# ATtiny_dev_board.net
KiCad netlist of a schematic drawn in EAGLE
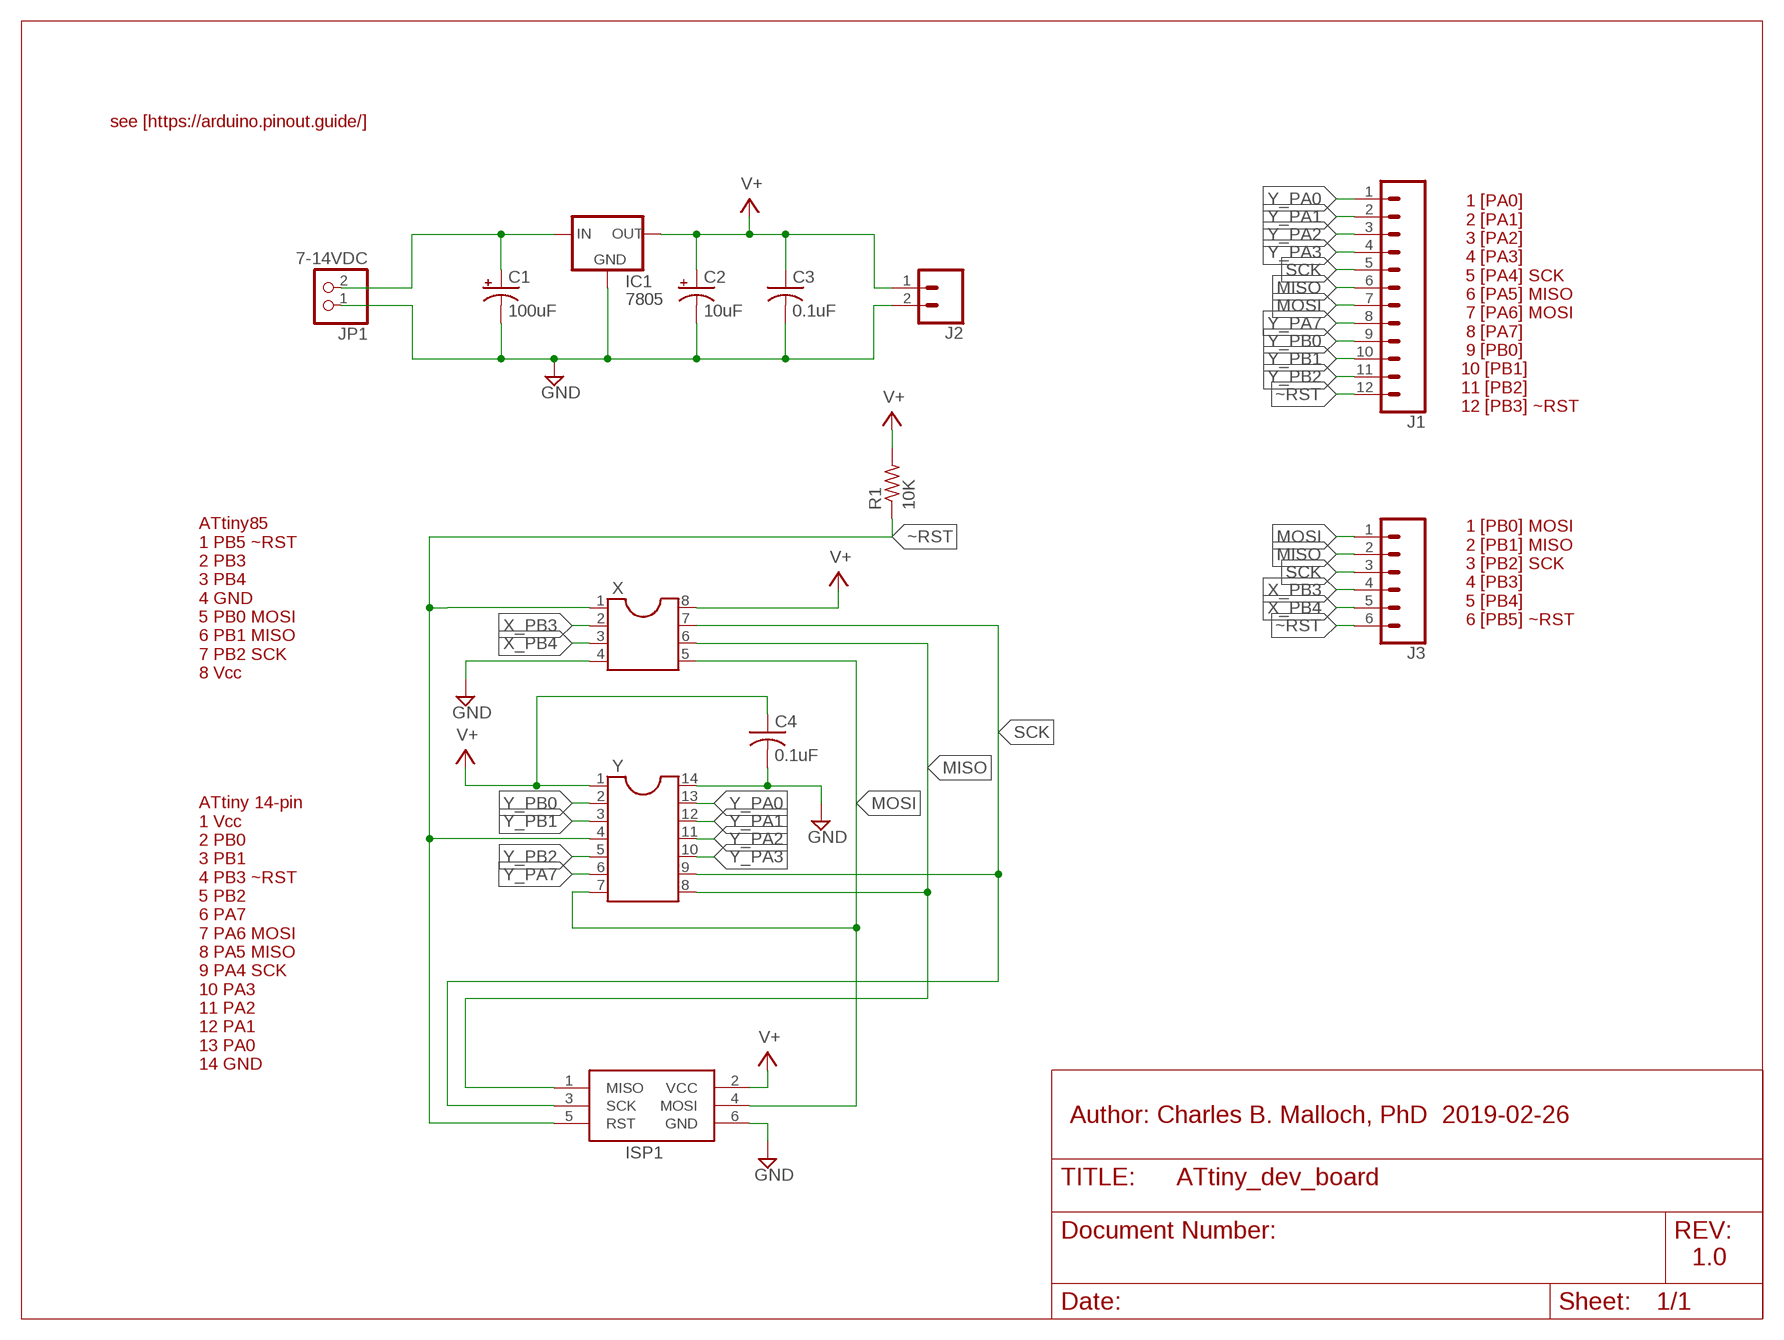
[diagram p0: schematic, sheet 1]

(export (version "E")
  (design (tool "Eeschema 10.0.6"))
  (components
    (comp (ref "C1")
      (value "100uF")
      (footprint "eagle-import:TT2D7")
      (libsource (lib "eagle-import") (part "CPOL-USTT2D7"))
    )
    (comp (ref "C2")
      (value "10uF")
      (footprint "eagle-import:E1,8-4")
      (libsource (lib "eagle-import") (part "CPOL-USE1.8-4"))
    )
    (comp (ref "C3")
      (value "0.1uF")
      (footprint "eagle-import:C025-025X050")
      (libsource (lib "eagle-import") (part "C-US025-025X050"))
    )
    (comp (ref "C4")
      (value "0.1uF")
      (footprint "eagle-import:C025-025X050")
      (libsource (lib "eagle-import") (part "C-US025-025X050"))
    )
    (comp (ref "IC1")
      (value "7805")
      (footprint "eagle-import:TO-220-ALT")
      (libsource (lib "eagle-import") (part "V_REG_78XX-TO-220"))
    )
    (comp (ref "ISP1")
      (value "AVRISP-BOX")
      (footprint "eagle-import:AVRISP-BOX")
      (libsource (lib "eagle-import") (part "AVRISP-BOX"))
    )
    (comp (ref "J1")
      (value "CONN_12LOCK_LONGPADS")
      (footprint "eagle-import:1X12_LOCK_LONGPADS")
      (libsource (lib "eagle-import") (part "CONN_12LOCK_LONGPADS"))
    )
    (comp (ref "J2")
      (value "CONN_02LOCK_LONGPADS")
      (footprint "eagle-import:1X02_LOCK_LONGPADS")
      (libsource (lib "eagle-import") (part "CONN_02LOCK_LONGPADS"))
    )
    (comp (ref "J3")
      (value "CONN_06LOCK_LONGPADS")
      (footprint "eagle-import:1X06_LOCK_LONGPADS")
      (libsource (lib "eagle-import") (part "CONN_06LOCK_LONGPADS"))
    )
    (comp (ref "JP1")
      (value "7-14VDC")
      (footprint "eagle-import:1X02")
      (libsource (lib "eagle-import") (part "PINHD-1X2"))
    )
    (comp (ref "R1")
      (value "10K")
      (footprint "eagle-import:0309_12")
      (libsource (lib "eagle-import") (part "R-US_0309/12"))
    )
    (comp (ref "X")
      (value "DIL8S")
      (footprint "eagle-import:SOCKET-08")
      (libsource (lib "eagle-import") (part "DIL8S"))
    )
    (comp (ref "Y")
      (value "DIL14S")
      (footprint "eagle-import:SOCKET-14")
      (libsource (lib "eagle-import") (part "DIL14S"))
    )
  )
  (nets
    (net (code "1") (name "/~{RST}") (class "Default")
      (node (ref "ISP1") (pin "5") (pinfunction "RST_5") (pintype "output"))
      (node (ref "J1") (pin "12") (pinfunction "12_12") (pintype "passive"))
      (node (ref "J3") (pin "6") (pinfunction "6_6") (pintype "passive"))
      (node (ref "R1") (pin "1") (pinfunction "1_1") (pintype "passive"))
      (node (ref "X") (pin "1") (pinfunction "1_1") (pintype "passive"))
      (node (ref "Y") (pin "4") (pinfunction "4_4") (pintype "passive"))
    )
    (net (code "2") (name "GND") (class "Default")
      (node (ref "C1") (pin "-") (pinfunction "-_-") (pintype "passive"))
      (node (ref "C2") (pin "-") (pinfunction "-_-") (pintype "passive"))
      (node (ref "C3") (pin "2") (pinfunction "2_2") (pintype "passive"))
      (node (ref "C4") (pin "2") (pinfunction "2_2") (pintype "passive"))
      (node (ref "IC1") (pin "GND") (pinfunction "GND_GND") (pintype "input"))
      (node (ref "ISP1") (pin "6") (pinfunction "GND_6") (pintype "power_in"))
      (node (ref "J2") (pin "2") (pinfunction "2_2") (pintype "passive"))
      (node (ref "JP1") (pin "1") (pinfunction "1_1") (pintype "passive"))
      (node (ref "X") (pin "4") (pinfunction "4_4") (pintype "passive"))
      (node (ref "Y") (pin "14") (pinfunction "14_14") (pintype "passive"))
    )
    (net (code "3") (name "MISO") (class "Default")
      (node (ref "ISP1") (pin "1") (pinfunction "MISO_1") (pintype "input"))
      (node (ref "J1") (pin "6") (pinfunction "6_6") (pintype "passive"))
      (node (ref "J3") (pin "2") (pinfunction "2_2") (pintype "passive"))
      (node (ref "X") (pin "6") (pinfunction "6_6") (pintype "passive"))
      (node (ref "Y") (pin "8") (pinfunction "8_8") (pintype "passive"))
    )
    (net (code "4") (name "MOSI") (class "Default")
      (node (ref "ISP1") (pin "4") (pinfunction "MOSI_4") (pintype "output"))
      (node (ref "J1") (pin "7") (pinfunction "7_7") (pintype "passive"))
      (node (ref "J3") (pin "1") (pinfunction "1_1") (pintype "passive"))
      (node (ref "X") (pin "5") (pinfunction "5_5") (pintype "passive"))
      (node (ref "Y") (pin "7") (pinfunction "7_7") (pintype "passive"))
    )
    (net (code "5") (name "Net-(C1-Pad+)") (class "Default")
      (node (ref "C1") (pin "+") (pinfunction "+_+") (pintype "passive"))
      (node (ref "IC1") (pin "IN") (pinfunction "IN_IN") (pintype "input"))
      (node (ref "JP1") (pin "2") (pinfunction "2_2") (pintype "passive"))
    )
    (net (code "6") (name "SCK") (class "Default")
      (node (ref "ISP1") (pin "3") (pinfunction "SCK_3") (pintype "output"))
      (node (ref "J1") (pin "5") (pinfunction "5_5") (pintype "passive"))
      (node (ref "J3") (pin "3") (pinfunction "3_3") (pintype "passive"))
      (node (ref "X") (pin "7") (pinfunction "7_7") (pintype "passive"))
      (node (ref "Y") (pin "9") (pinfunction "9_9") (pintype "passive"))
    )
    (net (code "7") (name "V+") (class "Default")
      (node (ref "C2") (pin "+") (pinfunction "+_+") (pintype "passive"))
      (node (ref "C3") (pin "1") (pinfunction "1_1") (pintype "passive"))
      (node (ref "C4") (pin "1") (pinfunction "1_1") (pintype "passive"))
      (node (ref "IC1") (pin "OUT") (pinfunction "OUT_OUT") (pintype "output"))
      (node (ref "ISP1") (pin "2") (pinfunction "VCC_2") (pintype "power_in"))
      (node (ref "J2") (pin "1") (pinfunction "1_1") (pintype "passive"))
      (node (ref "R1") (pin "2") (pinfunction "2_2") (pintype "passive"))
      (node (ref "X") (pin "8") (pinfunction "8_8") (pintype "passive"))
      (node (ref "Y") (pin "1") (pinfunction "1_1") (pintype "passive"))
    )
    (net (code "8") (name "X_PB3") (class "Default")
      (node (ref "J3") (pin "4") (pinfunction "4_4") (pintype "passive"))
      (node (ref "X") (pin "2") (pinfunction "2_2") (pintype "passive"))
    )
    (net (code "9") (name "X_PB4") (class "Default")
      (node (ref "J3") (pin "5") (pinfunction "5_5") (pintype "passive"))
      (node (ref "X") (pin "3") (pinfunction "3_3") (pintype "passive"))
    )
    (net (code "10") (name "Y_PA0") (class "Default")
      (node (ref "J1") (pin "1") (pinfunction "1_1") (pintype "passive"))
      (node (ref "Y") (pin "13") (pinfunction "13_13") (pintype "passive"))
    )
    (net (code "11") (name "Y_PA1") (class "Default")
      (node (ref "J1") (pin "2") (pinfunction "2_2") (pintype "passive"))
      (node (ref "Y") (pin "12") (pinfunction "12_12") (pintype "passive"))
    )
    (net (code "12") (name "Y_PA2") (class "Default")
      (node (ref "J1") (pin "3") (pinfunction "3_3") (pintype "passive"))
      (node (ref "Y") (pin "11") (pinfunction "11_11") (pintype "passive"))
    )
    (net (code "13") (name "Y_PA3") (class "Default")
      (node (ref "J1") (pin "4") (pinfunction "4_4") (pintype "passive"))
      (node (ref "Y") (pin "10") (pinfunction "10_10") (pintype "passive"))
    )
    (net (code "14") (name "Y_PA7") (class "Default")
      (node (ref "J1") (pin "8") (pinfunction "8_8") (pintype "passive"))
      (node (ref "Y") (pin "6") (pinfunction "6_6") (pintype "passive"))
    )
    (net (code "15") (name "Y_PB0") (class "Default")
      (node (ref "J1") (pin "9") (pinfunction "9_9") (pintype "passive"))
      (node (ref "Y") (pin "2") (pinfunction "2_2") (pintype "passive"))
    )
    (net (code "16") (name "Y_PB1") (class "Default")
      (node (ref "J1") (pin "10") (pinfunction "10_10") (pintype "passive"))
      (node (ref "Y") (pin "3") (pinfunction "3_3") (pintype "passive"))
    )
    (net (code "17") (name "Y_PB2") (class "Default")
      (node (ref "J1") (pin "11") (pinfunction "11_11") (pintype "passive"))
      (node (ref "Y") (pin "5") (pinfunction "5_5") (pintype "passive"))
    )
  )
)
